# Fonte.net
KiCad netlist of a schematic drawn in EAGLE
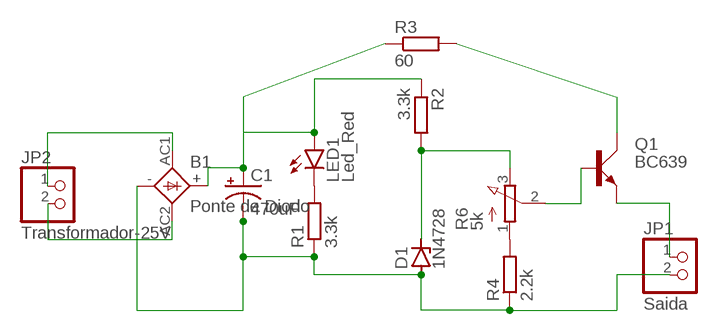
[diagram p0: schematic, sheet 1]

(export (version "E")
  (design (tool "Eeschema 10.0.6"))
  (components
    (comp (ref "B1")
      (value "Ponte de Diodo")
      (footprint "eagle-import:1KAB")
      (libsource (lib "eagle-import") (part "1KAB"))
    )
    (comp (ref "C1")
      (value "470uF")
      (footprint "eagle-import:E7,5-16")
      (libsource (lib "eagle-import") (part "CPOL-USE7.5-16"))
    )
    (comp (ref "D1")
      (value "1N4728")
      (footprint "eagle-import:DO41Z10")
      (libsource (lib "eagle-import") (part "1N4728"))
    )
    (comp (ref "JP1")
      (value "Saida")
      (footprint "eagle-import:1X02")
      (libsource (lib "eagle-import") (part "PINHD-1X2"))
    )
    (comp (ref "JP2")
      (value "Transformador-25V")
      (footprint "eagle-import:1X02")
      (libsource (lib "eagle-import") (part "PINHD-1X2"))
    )
    (comp (ref "LED1")
      (value "Led_Red")
      (footprint "eagle-import:LED5MM")
      (libsource (lib "eagle-import") (part "LED5MM"))
    )
    (comp (ref "Q1")
      (value "BC639")
      (footprint "eagle-import:SOT54D")
      (libsource (lib "eagle-import") (part "BC639"))
    )
    (comp (ref "R1")
      (value "3.3k")
      (footprint "eagle-import:0207_10")
      (libsource (lib "eagle-import") (part "R-EU_0207/10"))
    )
    (comp (ref "R2")
      (value "3.3k")
      (footprint "eagle-import:0207_10")
      (libsource (lib "eagle-import") (part "R-EU_0207/10"))
    )
    (comp (ref "R3")
      (value "60")
      (footprint "eagle-import:0309_10")
      (libsource (lib "eagle-import") (part "R-EU_0309/10"))
    )
    (comp (ref "R4")
      (value "2.2k")
      (footprint "eagle-import:0207_12")
      (libsource (lib "eagle-import") (part "R-EU_0207/12"))
    )
    (comp (ref "R6")
      (value "5k")
      (footprint "eagle-import:3RP_1610N")
      (libsource (lib "eagle-import") (part "3RP/1610N"))
    )
  )
  (nets
    (net (code "1") (name "Net-(B1-Pad+)") (class "Default")
      (node (ref "B1") (pin "+") (pinfunction "+_+") (pintype "passive"))
      (node (ref "C1") (pin "+") (pinfunction "+_+") (pintype "passive"))
      (node (ref "LED1") (pin "A") (pinfunction "A_A") (pintype "passive"))
      (node (ref "R2") (pin "1") (pinfunction "1_1") (pintype "passive"))
      (node (ref "R3") (pin "1") (pinfunction "1_1") (pintype "passive"))
    )
    (net (code "2") (name "Net-(B1-Pad-)") (class "Default")
      (node (ref "B1") (pin "-") (pinfunction "-_-") (pintype "passive"))
      (node (ref "C1") (pin "-") (pinfunction "-_-") (pintype "passive"))
      (node (ref "D1") (pin "A") (pinfunction "A_A") (pintype "passive"))
      (node (ref "JP1") (pin "2") (pinfunction "2_2") (pintype "passive"))
      (node (ref "R1") (pin "1") (pinfunction "1_1") (pintype "passive"))
      (node (ref "R4") (pin "1") (pinfunction "1_1") (pintype "passive"))
    )
    (net (code "3") (name "Net-(B1-PadAC1)") (class "Default")
      (node (ref "B1") (pin "AC1") (pinfunction "AC1_AC1") (pintype "passive"))
      (node (ref "JP2") (pin "1") (pinfunction "1_1") (pintype "passive"))
    )
    (net (code "4") (name "Net-(B1-PadAC2)") (class "Default")
      (node (ref "B1") (pin "AC2") (pinfunction "AC2_AC2") (pintype "passive"))
      (node (ref "JP2") (pin "2") (pinfunction "2_2") (pintype "passive"))
    )
    (net (code "5") (name "Net-(JP1-Pad1)") (class "Default")
      (node (ref "JP1") (pin "1") (pinfunction "1_1") (pintype "passive"))
      (node (ref "Q1") (pin "E") (pinfunction "E_E") (pintype "passive"))
    )
    (net (code "6") (name "Net-(LED1-C)") (class "Default")
      (node (ref "LED1") (pin "K") (pinfunction "C_K") (pintype "passive"))
      (node (ref "R1") (pin "2") (pinfunction "2_2") (pintype "passive"))
    )
    (net (code "7") (name "Net-(Q1-PadC)") (class "Default")
      (node (ref "Q1") (pin "C") (pinfunction "C_C") (pintype "passive"))
      (node (ref "R3") (pin "2") (pinfunction "2_2") (pintype "passive"))
    )
    (net (code "8") (name "Net-(R6-A)") (class "Default")
      (node (ref "R4") (pin "2") (pinfunction "2_2") (pintype "passive"))
      (node (ref "R6") (pin "1") (pinfunction "A_1") (pintype "passive"))
    )
    (net (code "9") (name "Net-(R6-E)") (class "Default")
      (node (ref "D1") (pin "C") (pinfunction "C_C") (pintype "passive"))
      (node (ref "R2") (pin "2") (pinfunction "2_2") (pintype "passive"))
      (node (ref "R6") (pin "3") (pinfunction "E_3") (pintype "passive"))
    )
    (net (code "10") (name "Net-(R6-S)") (class "Default")
      (node (ref "Q1") (pin "B") (pinfunction "B_B") (pintype "passive"))
      (node (ref "R6") (pin "2") (pinfunction "S_2") (pintype "passive"))
    )
  )
)
